# Ada_-_Base_Block_-_Daughter_Board_4_0.net
KiCad netlist of a schematic drawn in Altium Designer
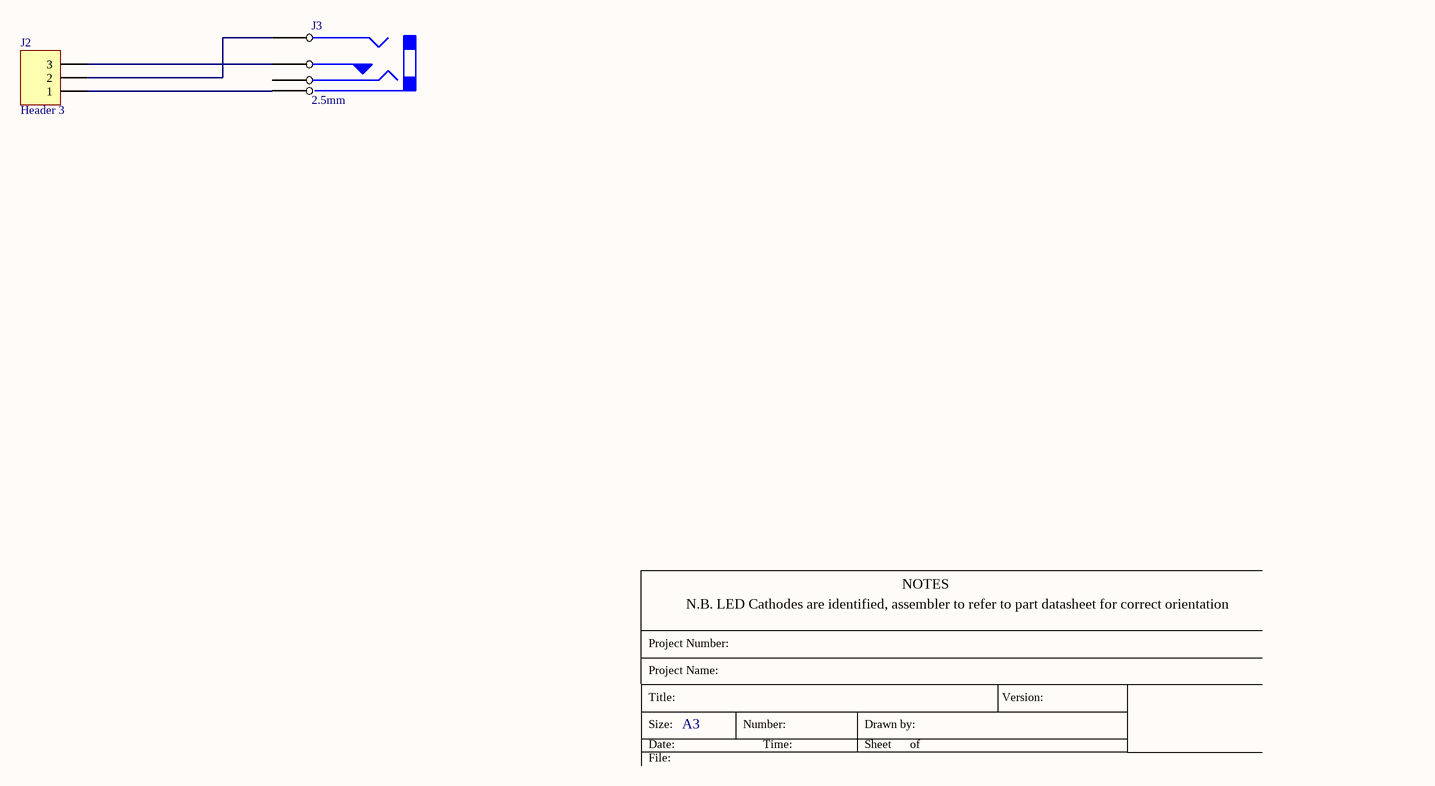
[diagram p0: Ada - Base Block - Daughter Board 4.0.SchDoc]

(export (version "E")
  (design (tool "Eeschema 10.0.6"))
  (components
    (comp (ref "J2")
      (value "Header 3")
      (footprint "sip3")
      (description "Header, 3-Pin")
      (libsource (lib "Connectors") (part "Header 3"))
    )
    (comp (ref "J3")
      (value "2.5mm")
      (footprint "2.5mm socket TRI001")
      (description "2.5mm PHONEJACK STEREO")
      (fields (field (name "MANUFACTURER") "PRO SIGNAL") (field (name "MANUF PART #") "PSG01539"))
      (libsource (lib "Connectors") (part "2.5mm PHONEJACK STEREO TRI001"))
    )
  )
  (nets
    (net (code "1") (name "Net-(J2-Pad1)") (class "Default")
      (node (ref "J2") (pin "1") (pinfunction "1_1") (pintype "passive"))
      (node (ref "J3") (pin "1") (pinfunction "1_1") (pintype "passive"))
    )
    (net (code "2") (name "Net-(J2-Pad2)") (class "Default")
      (node (ref "J2") (pin "2") (pinfunction "2_2") (pintype "passive"))
      (node (ref "J3") (pin "4") (pinfunction "4_4") (pintype "passive"))
    )
    (net (code "3") (name "Net-(J2-Pad3)") (class "Default")
      (node (ref "J2") (pin "3") (pinfunction "3_3") (pintype "passive"))
      (node (ref "J3") (pin "2") (pinfunction "2_2") (pintype "passive"))
    )
    (net (code "4") (name "unconnected-(J3-Pad3)") (class "Default")
      (node (ref "J3") (pin "3") (pinfunction "3_3") (pintype "passive"))
    )
  )
)
